# Osmofl2k_adapter_zmatch.net
KiCad netlist of a schematic drawn in EAGLE
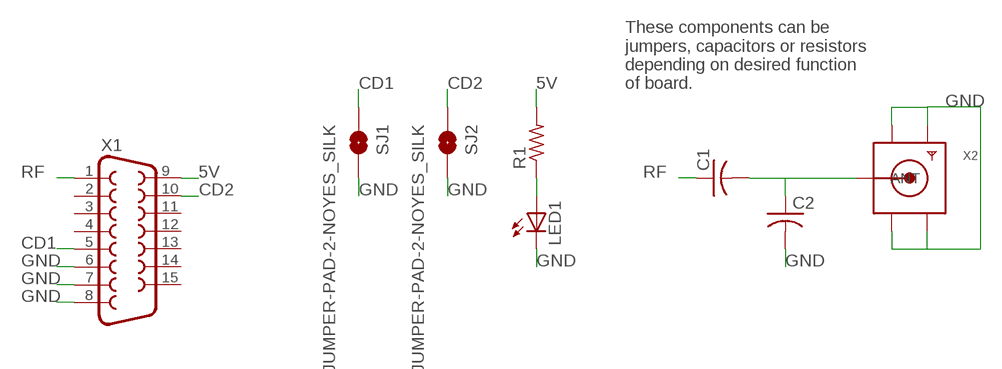
[diagram p0: schematic, sheet 1]

(export (version "E")
  (design (tool "Eeschema 10.0.6"))
  (components
    (comp (ref "C1")
      (value "C-USC0603")
      (footprint "eagle-import:C0603")
      (libsource (lib "eagle-import") (part "C-USC0603"))
    )
    (comp (ref "C2")
      (value "C-USC0603")
      (footprint "eagle-import:C0603")
      (libsource (lib "eagle-import") (part "C-USC0603"))
    )
    (comp (ref "LED1")
      (value "LEDCHIPLED_0805")
      (footprint "eagle-import:CHIPLED_0805")
      (libsource (lib "eagle-import") (part "LEDCHIPLED_0805"))
    )
    (comp (ref "R1")
      (value "R-US_R0805")
      (footprint "eagle-import:R0805")
      (libsource (lib "eagle-import") (part "R-US_R0805"))
    )
    (comp (ref "SJ1")
      (value "JUMPER-PAD-2-NOYES_SILK")
      (footprint "eagle-import:PAD-JUMPER-2-NO_YES_SILK")
      (libsource (lib "eagle-import") (part "JUMPER-PAD-2-NOYES_SILK"))
    )
    (comp (ref "SJ2")
      (value "JUMPER-PAD-2-NOYES_SILK")
      (footprint "eagle-import:PAD-JUMPER-2-NO_YES_SILK")
      (libsource (lib "eagle-import") (part "JUMPER-PAD-2-NOYES_SILK"))
    )
    (comp (ref "X1")
      (value "F15HDH")
      (footprint "eagle-import:HDF15H")
      (libsource (lib "eagle-import") (part "F15HDH"))
    )
    (comp (ref "X2")
      (value "SMACONNECTOR_EDGE")
      (footprint "eagle-import:SMA_EDGELAUNCH")
      (libsource (lib "eagle-import") (part "SMACONNECTOR_EDGE"))
    )
  )
  (nets
    (net (code "1") (name "/5V") (class "Default")
      (node (ref "R1") (pin "2") (pinfunction "2_2") (pintype "passive"))
      (node (ref "X1") (pin "9") (pinfunction "9_9") (pintype "passive"))
    )
    (net (code "2") (name "/CD1") (class "Default")
      (node (ref "SJ1") (pin "1") (pinfunction "1_1") (pintype "passive"))
      (node (ref "X1") (pin "5") (pinfunction "5_5") (pintype "passive"))
    )
    (net (code "3") (name "/CD2") (class "Default")
      (node (ref "SJ2") (pin "1") (pinfunction "1_1") (pintype "passive"))
      (node (ref "X1") (pin "10") (pinfunction "10_10") (pintype "passive"))
    )
    (net (code "4") (name "/GND") (class "Default")
      (node (ref "C2") (pin "2") (pinfunction "2_2") (pintype "passive"))
      (node (ref "LED1") (pin "C") (pinfunction "C_C") (pintype "passive"))
      (node (ref "SJ1") (pin "2") (pinfunction "2_2") (pintype "passive"))
      (node (ref "SJ2") (pin "2") (pinfunction "2_2") (pintype "passive"))
      (node (ref "X1") (pin "6") (pinfunction "6_6") (pintype "passive"))
      (node (ref "X1") (pin "7") (pinfunction "7_7") (pintype "passive"))
      (node (ref "X1") (pin "8") (pinfunction "8_8") (pintype "passive"))
      (node (ref "X2") (pin "GND@1") (pinfunction "GND4_GND@1") (pintype "power_in"))
      (node (ref "X2") (pin "GND@2") (pinfunction "GND3_GND@2") (pintype "power_in"))
      (node (ref "X2") (pin "GND@3") (pinfunction "GND2_GND@3") (pintype "power_in"))
      (node (ref "X2") (pin "GND@4") (pinfunction "GND1_GND@4") (pintype "power_in"))
    )
    (net (code "5") (name "/RF") (class "Default")
      (node (ref "C1") (pin "1") (pinfunction "1_1") (pintype "passive"))
      (node (ref "X1") (pin "1") (pinfunction "1_1") (pintype "passive"))
    )
    (net (code "6") (name "Net-(LED1-PadA)") (class "Default")
      (node (ref "LED1") (pin "A") (pinfunction "A_A") (pintype "passive"))
      (node (ref "R1") (pin "1") (pinfunction "1_1") (pintype "passive"))
    )
    (net (code "7") (name "Net-(X2-ANT)") (class "Default")
      (node (ref "C1") (pin "2") (pinfunction "2_2") (pintype "passive"))
      (node (ref "C2") (pin "1") (pinfunction "1_1") (pintype "passive"))
      (node (ref "X2") (pin "P") (pinfunction "ANT_P") (pintype "bidirectional"))
    )
    (net (code "8") (name "unconnected-(X1-Pad2)") (class "Default")
      (node (ref "X1") (pin "2") (pinfunction "2_2") (pintype "passive"))
    )
    (net (code "9") (name "unconnected-(X1-Pad3)") (class "Default")
      (node (ref "X1") (pin "3") (pinfunction "3_3") (pintype "passive"))
    )
    (net (code "10") (name "unconnected-(X1-Pad4)") (class "Default")
      (node (ref "X1") (pin "4") (pinfunction "4_4") (pintype "passive"))
    )
    (net (code "11") (name "unconnected-(X1-Pad11)") (class "Default")
      (node (ref "X1") (pin "11") (pinfunction "11_11") (pintype "passive"))
    )
    (net (code "12") (name "unconnected-(X1-Pad12)") (class "Default")
      (node (ref "X1") (pin "12") (pinfunction "12_12") (pintype "passive"))
    )
    (net (code "13") (name "unconnected-(X1-Pad13)") (class "Default")
      (node (ref "X1") (pin "13") (pinfunction "13_13") (pintype "passive"))
    )
    (net (code "14") (name "unconnected-(X1-Pad14)") (class "Default")
      (node (ref "X1") (pin "14") (pinfunction "14_14") (pintype "passive"))
    )
    (net (code "15") (name "unconnected-(X1-Pad15)") (class "Default")
      (node (ref "X1") (pin "15") (pinfunction "15_15") (pintype "passive"))
    )
  )
)
